# 20260106.net
KiCad netlist of a schematic drawn in EasyEDA Pro
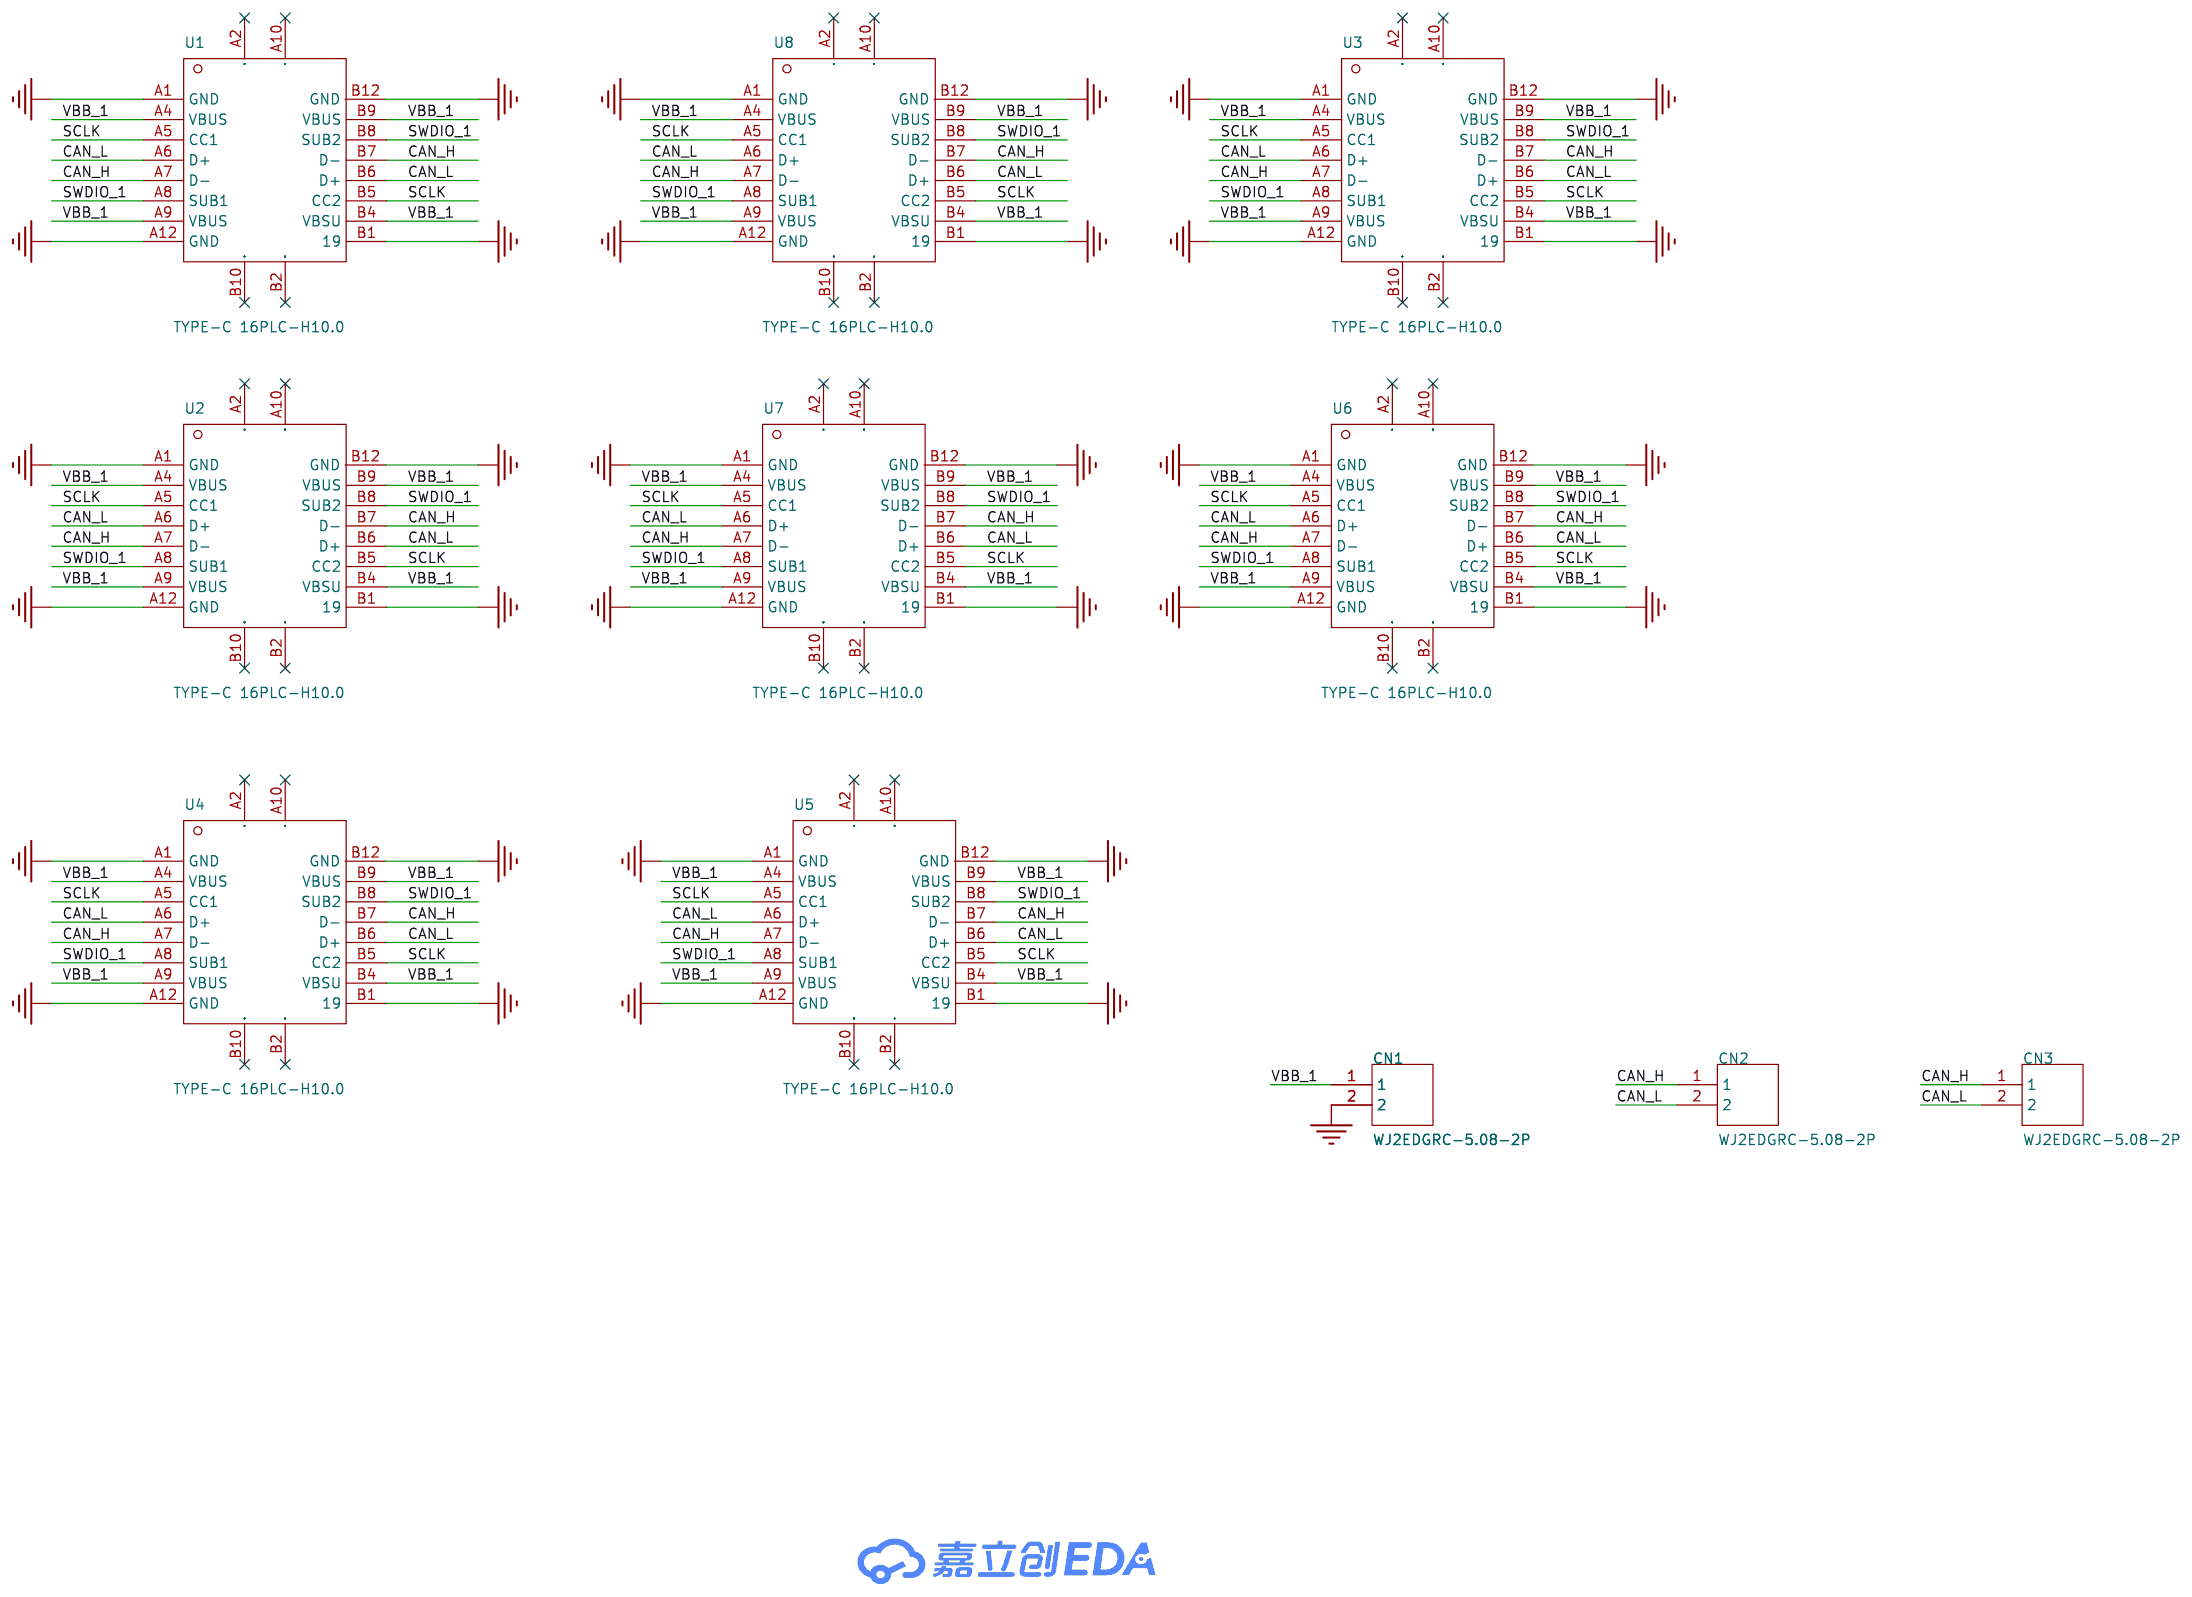
[diagram p0: schematic sheet]

(export (version "E")
  (design (tool "Eeschema 10.0.6"))
  (components
    (comp (ref "CN1")
      (value "WJ2EDGRC-5.08-2P")
      (footprint "easyedapro:CONN-TH_2P-P5.08_WJ2EDGRC-5.08-2P")
      (fields (field (name "Manufacturer") "KANGNEX(康奈克斯电气)"))
      (libsource (lib "easyedapro") (part "WJ2EDGRC-5.08-2P"))
    )
    (comp (ref "CN2")
      (value "WJ2EDGRC-5.08-2P")
      (footprint "easyedapro:CONN-TH_2P-P5.08_WJ2EDGRC-5.08-2P")
      (fields (field (name "Manufacturer") "KANGNEX(康奈克斯电气)"))
      (libsource (lib "easyedapro") (part "WJ2EDGRC-5.08-2P"))
    )
    (comp (ref "CN3")
      (value "WJ2EDGRC-5.08-2P")
      (footprint "easyedapro:CONN-TH_2P-P5.08_WJ2EDGRC-5.08-2P")
      (fields (field (name "Manufacturer") "KANGNEX(康奈克斯电气)"))
      (libsource (lib "easyedapro") (part "WJ2EDGRC-5.08-2P"))
    )
    (comp (ref "U1")
      (value "TYPE-C 16PLC-H10.0")
      (footprint "easyedapro:TYPE-C-TH_16PLC-H10.0")
      (fields (field (name "Manufacturer") "SHOU HAN(首韩)"))
      (libsource (lib "easyedapro") (part "TYPE-C 16PLC-H10.0"))
    )
    (comp (ref "U2")
      (value "TYPE-C 16PLC-H10.0")
      (footprint "easyedapro:TYPE-C-TH_16PLC-H10.0")
      (fields (field (name "Manufacturer") "SHOU HAN(首韩)"))
      (libsource (lib "easyedapro") (part "TYPE-C 16PLC-H10.0"))
    )
    (comp (ref "U3")
      (value "TYPE-C 16PLC-H10.0")
      (footprint "easyedapro:TYPE-C-TH_16PLC-H10.0")
      (fields (field (name "Manufacturer") "SHOU HAN(首韩)"))
      (libsource (lib "easyedapro") (part "TYPE-C 16PLC-H10.0"))
    )
    (comp (ref "U4")
      (value "TYPE-C 16PLC-H10.0")
      (footprint "easyedapro:TYPE-C-TH_16PLC-H10.0")
      (fields (field (name "Manufacturer") "SHOU HAN(首韩)"))
      (libsource (lib "easyedapro") (part "TYPE-C 16PLC-H10.0"))
    )
    (comp (ref "U5")
      (value "TYPE-C 16PLC-H10.0")
      (footprint "easyedapro:TYPE-C-TH_16PLC-H10.0")
      (fields (field (name "Manufacturer") "SHOU HAN(首韩)"))
      (libsource (lib "easyedapro") (part "TYPE-C 16PLC-H10.0"))
    )
    (comp (ref "U6")
      (value "TYPE-C 16PLC-H10.0")
      (footprint "easyedapro:TYPE-C-TH_16PLC-H10.0")
      (fields (field (name "Manufacturer") "SHOU HAN(首韩)"))
      (libsource (lib "easyedapro") (part "TYPE-C 16PLC-H10.0"))
    )
    (comp (ref "U7")
      (value "TYPE-C 16PLC-H10.0")
      (footprint "easyedapro:TYPE-C-TH_16PLC-H10.0")
      (fields (field (name "Manufacturer") "SHOU HAN(首韩)"))
      (libsource (lib "easyedapro") (part "TYPE-C 16PLC-H10.0"))
    )
    (comp (ref "U8")
      (value "TYPE-C 16PLC-H10.0")
      (footprint "easyedapro:TYPE-C-TH_16PLC-H10.0")
      (fields (field (name "Manufacturer") "SHOU HAN(首韩)"))
      (libsource (lib "easyedapro") (part "TYPE-C 16PLC-H10.0"))
    )
  )
  (nets
    (net (code "1") (name "/CAN_H") (class "Default")
      (node (ref "CN2") (pin "1") (pinfunction "1_1") (pintype "unspecified"))
      (node (ref "CN3") (pin "1") (pinfunction "1_1") (pintype "unspecified"))
      (node (ref "U1") (pin "A7") (pinfunction "D-_A7") (pintype "input"))
      (node (ref "U1") (pin "B7") (pinfunction "D-_B7") (pintype "input"))
      (node (ref "U2") (pin "A7") (pinfunction "D-_A7") (pintype "input"))
      (node (ref "U2") (pin "B7") (pinfunction "D-_B7") (pintype "input"))
      (node (ref "U3") (pin "A7") (pinfunction "D-_A7") (pintype "input"))
      (node (ref "U3") (pin "B7") (pinfunction "D-_B7") (pintype "input"))
      (node (ref "U4") (pin "A7") (pinfunction "D-_A7") (pintype "input"))
      (node (ref "U4") (pin "B7") (pinfunction "D-_B7") (pintype "input"))
      (node (ref "U5") (pin "A7") (pinfunction "D-_A7") (pintype "input"))
      (node (ref "U5") (pin "B7") (pinfunction "D-_B7") (pintype "input"))
      (node (ref "U6") (pin "A7") (pinfunction "D-_A7") (pintype "input"))
      (node (ref "U6") (pin "B7") (pinfunction "D-_B7") (pintype "input"))
      (node (ref "U7") (pin "A7") (pinfunction "D-_A7") (pintype "input"))
      (node (ref "U7") (pin "B7") (pinfunction "D-_B7") (pintype "input"))
      (node (ref "U8") (pin "A7") (pinfunction "D-_A7") (pintype "input"))
      (node (ref "U8") (pin "B7") (pinfunction "D-_B7") (pintype "input"))
    )
    (net (code "2") (name "/CAN_L") (class "Default")
      (node (ref "CN2") (pin "2") (pinfunction "2_2") (pintype "unspecified"))
      (node (ref "CN3") (pin "2") (pinfunction "2_2") (pintype "unspecified"))
      (node (ref "U1") (pin "A6") (pinfunction "D+_A6") (pintype "input"))
      (node (ref "U1") (pin "B6") (pinfunction "D+_B6") (pintype "input"))
      (node (ref "U2") (pin "A6") (pinfunction "D+_A6") (pintype "input"))
      (node (ref "U2") (pin "B6") (pinfunction "D+_B6") (pintype "input"))
      (node (ref "U3") (pin "A6") (pinfunction "D+_A6") (pintype "input"))
      (node (ref "U3") (pin "B6") (pinfunction "D+_B6") (pintype "input"))
      (node (ref "U4") (pin "A6") (pinfunction "D+_A6") (pintype "input"))
      (node (ref "U4") (pin "B6") (pinfunction "D+_B6") (pintype "input"))
      (node (ref "U5") (pin "A6") (pinfunction "D+_A6") (pintype "input"))
      (node (ref "U5") (pin "B6") (pinfunction "D+_B6") (pintype "input"))
      (node (ref "U6") (pin "A6") (pinfunction "D+_A6") (pintype "input"))
      (node (ref "U6") (pin "B6") (pinfunction "D+_B6") (pintype "input"))
      (node (ref "U7") (pin "A6") (pinfunction "D+_A6") (pintype "input"))
      (node (ref "U7") (pin "B6") (pinfunction "D+_B6") (pintype "input"))
      (node (ref "U8") (pin "A6") (pinfunction "D+_A6") (pintype "input"))
      (node (ref "U8") (pin "B6") (pinfunction "D+_B6") (pintype "input"))
    )
    (net (code "3") (name "/SCLK") (class "Default")
      (node (ref "U1") (pin "A5") (pinfunction "CC1_A5") (pintype "input"))
      (node (ref "U1") (pin "B5") (pinfunction "CC2_B5") (pintype "input"))
      (node (ref "U2") (pin "A5") (pinfunction "CC1_A5") (pintype "input"))
      (node (ref "U2") (pin "B5") (pinfunction "CC2_B5") (pintype "input"))
      (node (ref "U3") (pin "A5") (pinfunction "CC1_A5") (pintype "input"))
      (node (ref "U3") (pin "B5") (pinfunction "CC2_B5") (pintype "input"))
      (node (ref "U4") (pin "A5") (pinfunction "CC1_A5") (pintype "input"))
      (node (ref "U4") (pin "B5") (pinfunction "CC2_B5") (pintype "input"))
      (node (ref "U5") (pin "A5") (pinfunction "CC1_A5") (pintype "input"))
      (node (ref "U5") (pin "B5") (pinfunction "CC2_B5") (pintype "input"))
      (node (ref "U6") (pin "A5") (pinfunction "CC1_A5") (pintype "input"))
      (node (ref "U6") (pin "B5") (pinfunction "CC2_B5") (pintype "input"))
      (node (ref "U7") (pin "A5") (pinfunction "CC1_A5") (pintype "input"))
      (node (ref "U7") (pin "B5") (pinfunction "CC2_B5") (pintype "input"))
      (node (ref "U8") (pin "A5") (pinfunction "CC1_A5") (pintype "input"))
      (node (ref "U8") (pin "B5") (pinfunction "CC2_B5") (pintype "input"))
    )
    (net (code "4") (name "/SWDIO_1") (class "Default")
      (node (ref "U1") (pin "A8") (pinfunction "SUB1_A8") (pintype "input"))
      (node (ref "U1") (pin "B8") (pinfunction "SUB2_B8") (pintype "input"))
      (node (ref "U2") (pin "A8") (pinfunction "SUB1_A8") (pintype "input"))
      (node (ref "U2") (pin "B8") (pinfunction "SUB2_B8") (pintype "input"))
      (node (ref "U3") (pin "A8") (pinfunction "SUB1_A8") (pintype "input"))
      (node (ref "U3") (pin "B8") (pinfunction "SUB2_B8") (pintype "input"))
      (node (ref "U4") (pin "A8") (pinfunction "SUB1_A8") (pintype "input"))
      (node (ref "U4") (pin "B8") (pinfunction "SUB2_B8") (pintype "input"))
      (node (ref "U5") (pin "A8") (pinfunction "SUB1_A8") (pintype "input"))
      (node (ref "U5") (pin "B8") (pinfunction "SUB2_B8") (pintype "input"))
      (node (ref "U6") (pin "A8") (pinfunction "SUB1_A8") (pintype "input"))
      (node (ref "U6") (pin "B8") (pinfunction "SUB2_B8") (pintype "input"))
      (node (ref "U7") (pin "A8") (pinfunction "SUB1_A8") (pintype "input"))
      (node (ref "U7") (pin "B8") (pinfunction "SUB2_B8") (pintype "input"))
      (node (ref "U8") (pin "A8") (pinfunction "SUB1_A8") (pintype "input"))
      (node (ref "U8") (pin "B8") (pinfunction "SUB2_B8") (pintype "input"))
    )
    (net (code "5") (name "/VBB_1") (class "Default")
      (node (ref "CN1") (pin "1") (pinfunction "1_1") (pintype "unspecified"))
      (node (ref "U1") (pin "A4") (pinfunction "VBUS_A4") (pintype "input"))
      (node (ref "U1") (pin "A9") (pinfunction "VBUS_A9") (pintype "input"))
      (node (ref "U1") (pin "B4") (pinfunction "VBSU_B4") (pintype "input"))
      (node (ref "U1") (pin "B9") (pinfunction "VBUS_B9") (pintype "input"))
      (node (ref "U2") (pin "A4") (pinfunction "VBUS_A4") (pintype "input"))
      (node (ref "U2") (pin "A9") (pinfunction "VBUS_A9") (pintype "input"))
      (node (ref "U2") (pin "B4") (pinfunction "VBSU_B4") (pintype "input"))
      (node (ref "U2") (pin "B9") (pinfunction "VBUS_B9") (pintype "input"))
      (node (ref "U3") (pin "A4") (pinfunction "VBUS_A4") (pintype "input"))
      (node (ref "U3") (pin "A9") (pinfunction "VBUS_A9") (pintype "input"))
      (node (ref "U3") (pin "B4") (pinfunction "VBSU_B4") (pintype "input"))
      (node (ref "U3") (pin "B9") (pinfunction "VBUS_B9") (pintype "input"))
      (node (ref "U4") (pin "A4") (pinfunction "VBUS_A4") (pintype "input"))
      (node (ref "U4") (pin "A9") (pinfunction "VBUS_A9") (pintype "input"))
      (node (ref "U4") (pin "B4") (pinfunction "VBSU_B4") (pintype "input"))
      (node (ref "U4") (pin "B9") (pinfunction "VBUS_B9") (pintype "input"))
      (node (ref "U5") (pin "A4") (pinfunction "VBUS_A4") (pintype "input"))
      (node (ref "U5") (pin "A9") (pinfunction "VBUS_A9") (pintype "input"))
      (node (ref "U5") (pin "B4") (pinfunction "VBSU_B4") (pintype "input"))
      (node (ref "U5") (pin "B9") (pinfunction "VBUS_B9") (pintype "input"))
      (node (ref "U6") (pin "A4") (pinfunction "VBUS_A4") (pintype "input"))
      (node (ref "U6") (pin "A9") (pinfunction "VBUS_A9") (pintype "input"))
      (node (ref "U6") (pin "B4") (pinfunction "VBSU_B4") (pintype "input"))
      (node (ref "U6") (pin "B9") (pinfunction "VBUS_B9") (pintype "input"))
      (node (ref "U7") (pin "A4") (pinfunction "VBUS_A4") (pintype "input"))
      (node (ref "U7") (pin "A9") (pinfunction "VBUS_A9") (pintype "input"))
      (node (ref "U7") (pin "B4") (pinfunction "VBSU_B4") (pintype "input"))
      (node (ref "U7") (pin "B9") (pinfunction "VBUS_B9") (pintype "input"))
      (node (ref "U8") (pin "A4") (pinfunction "VBUS_A4") (pintype "input"))
      (node (ref "U8") (pin "A9") (pinfunction "VBUS_A9") (pintype "input"))
      (node (ref "U8") (pin "B4") (pinfunction "VBSU_B4") (pintype "input"))
      (node (ref "U8") (pin "B9") (pinfunction "VBUS_B9") (pintype "input"))
    )
    (net (code "6") (name "GND") (class "Default")
      (node (ref "CN1") (pin "2") (pinfunction "2_2") (pintype "unspecified"))
      (node (ref "U1") (pin "A1") (pinfunction "GND_A1") (pintype "input"))
      (node (ref "U1") (pin "A12") (pinfunction "GND_A12") (pintype "input"))
      (node (ref "U1") (pin "B1") (pinfunction "19_B1") (pintype "input"))
      (node (ref "U1") (pin "B12") (pinfunction "GND_B12") (pintype "input"))
      (node (ref "U2") (pin "A1") (pinfunction "GND_A1") (pintype "input"))
      (node (ref "U2") (pin "A12") (pinfunction "GND_A12") (pintype "input"))
      (node (ref "U2") (pin "B1") (pinfunction "19_B1") (pintype "input"))
      (node (ref "U2") (pin "B12") (pinfunction "GND_B12") (pintype "input"))
      (node (ref "U3") (pin "A1") (pinfunction "GND_A1") (pintype "input"))
      (node (ref "U3") (pin "A12") (pinfunction "GND_A12") (pintype "input"))
      (node (ref "U3") (pin "B1") (pinfunction "19_B1") (pintype "input"))
      (node (ref "U3") (pin "B12") (pinfunction "GND_B12") (pintype "input"))
      (node (ref "U4") (pin "A1") (pinfunction "GND_A1") (pintype "input"))
      (node (ref "U4") (pin "A12") (pinfunction "GND_A12") (pintype "input"))
      (node (ref "U4") (pin "B1") (pinfunction "19_B1") (pintype "input"))
      (node (ref "U4") (pin "B12") (pinfunction "GND_B12") (pintype "input"))
      (node (ref "U5") (pin "A1") (pinfunction "GND_A1") (pintype "input"))
      (node (ref "U5") (pin "A12") (pinfunction "GND_A12") (pintype "input"))
      (node (ref "U5") (pin "B1") (pinfunction "19_B1") (pintype "input"))
      (node (ref "U5") (pin "B12") (pinfunction "GND_B12") (pintype "input"))
      (node (ref "U6") (pin "A1") (pinfunction "GND_A1") (pintype "input"))
      (node (ref "U6") (pin "A12") (pinfunction "GND_A12") (pintype "input"))
      (node (ref "U6") (pin "B1") (pinfunction "19_B1") (pintype "input"))
      (node (ref "U6") (pin "B12") (pinfunction "GND_B12") (pintype "input"))
      (node (ref "U7") (pin "A1") (pinfunction "GND_A1") (pintype "input"))
      (node (ref "U7") (pin "A12") (pinfunction "GND_A12") (pintype "input"))
      (node (ref "U7") (pin "B1") (pinfunction "19_B1") (pintype "input"))
      (node (ref "U7") (pin "B12") (pinfunction "GND_B12") (pintype "input"))
      (node (ref "U8") (pin "A1") (pinfunction "GND_A1") (pintype "input"))
      (node (ref "U8") (pin "A12") (pinfunction "GND_A12") (pintype "input"))
      (node (ref "U8") (pin "B1") (pinfunction "19_B1") (pintype "input"))
      (node (ref "U8") (pin "B12") (pinfunction "GND_B12") (pintype "input"))
    )
    (net (code "7") (name "unconnected-(U1-GND1-PadA2)") (class "Default")
      (node (ref "U1") (pin "A2") (pinfunction "GND1_A2") (pintype "input+no_connect"))
    )
    (net (code "8") (name "unconnected-(U1-GND2-PadA10)") (class "Default")
      (node (ref "U1") (pin "A10") (pinfunction "GND2_A10") (pintype "input+no_connect"))
    )
    (net (code "9") (name "unconnected-(U1-GND3-PadB10)") (class "Default")
      (node (ref "U1") (pin "B10") (pinfunction "GND3_B10") (pintype "input+no_connect"))
    )
    (net (code "10") (name "unconnected-(U1-GND4-PadB2)") (class "Default")
      (node (ref "U1") (pin "B2") (pinfunction "GND4_B2") (pintype "input+no_connect"))
    )
    (net (code "11") (name "unconnected-(U2-GND1-PadA2)") (class "Default")
      (node (ref "U2") (pin "A2") (pinfunction "GND1_A2") (pintype "input+no_connect"))
    )
    (net (code "12") (name "unconnected-(U2-GND2-PadA10)") (class "Default")
      (node (ref "U2") (pin "A10") (pinfunction "GND2_A10") (pintype "input+no_connect"))
    )
    (net (code "13") (name "unconnected-(U2-GND3-PadB10)") (class "Default")
      (node (ref "U2") (pin "B10") (pinfunction "GND3_B10") (pintype "input+no_connect"))
    )
    (net (code "14") (name "unconnected-(U2-GND4-PadB2)") (class "Default")
      (node (ref "U2") (pin "B2") (pinfunction "GND4_B2") (pintype "input+no_connect"))
    )
    (net (code "15") (name "unconnected-(U3-GND1-PadA2)") (class "Default")
      (node (ref "U3") (pin "A2") (pinfunction "GND1_A2") (pintype "input+no_connect"))
    )
    (net (code "16") (name "unconnected-(U3-GND2-PadA10)") (class "Default")
      (node (ref "U3") (pin "A10") (pinfunction "GND2_A10") (pintype "input+no_connect"))
    )
    (net (code "17") (name "unconnected-(U3-GND3-PadB10)") (class "Default")
      (node (ref "U3") (pin "B10") (pinfunction "GND3_B10") (pintype "input+no_connect"))
    )
    (net (code "18") (name "unconnected-(U3-GND4-PadB2)") (class "Default")
      (node (ref "U3") (pin "B2") (pinfunction "GND4_B2") (pintype "input+no_connect"))
    )
    (net (code "19") (name "unconnected-(U4-GND1-PadA2)") (class "Default")
      (node (ref "U4") (pin "A2") (pinfunction "GND1_A2") (pintype "input+no_connect"))
    )
    (net (code "20") (name "unconnected-(U4-GND2-PadA10)") (class "Default")
      (node (ref "U4") (pin "A10") (pinfunction "GND2_A10") (pintype "input+no_connect"))
    )
    (net (code "21") (name "unconnected-(U4-GND3-PadB10)") (class "Default")
      (node (ref "U4") (pin "B10") (pinfunction "GND3_B10") (pintype "input+no_connect"))
    )
    (net (code "22") (name "unconnected-(U4-GND4-PadB2)") (class "Default")
      (node (ref "U4") (pin "B2") (pinfunction "GND4_B2") (pintype "input+no_connect"))
    )
    (net (code "23") (name "unconnected-(U5-GND1-PadA2)") (class "Default")
      (node (ref "U5") (pin "A2") (pinfunction "GND1_A2") (pintype "input+no_connect"))
    )
    (net (code "24") (name "unconnected-(U5-GND2-PadA10)") (class "Default")
      (node (ref "U5") (pin "A10") (pinfunction "GND2_A10") (pintype "input+no_connect"))
    )
    (net (code "25") (name "unconnected-(U5-GND3-PadB10)") (class "Default")
      (node (ref "U5") (pin "B10") (pinfunction "GND3_B10") (pintype "input+no_connect"))
    )
    (net (code "26") (name "unconnected-(U5-GND4-PadB2)") (class "Default")
      (node (ref "U5") (pin "B2") (pinfunction "GND4_B2") (pintype "input+no_connect"))
    )
    (net (code "27") (name "unconnected-(U6-GND1-PadA2)") (class "Default")
      (node (ref "U6") (pin "A2") (pinfunction "GND1_A2") (pintype "input+no_connect"))
    )
    (net (code "28") (name "unconnected-(U6-GND2-PadA10)") (class "Default")
      (node (ref "U6") (pin "A10") (pinfunction "GND2_A10") (pintype "input+no_connect"))
    )
    (net (code "29") (name "unconnected-(U6-GND3-PadB10)") (class "Default")
      (node (ref "U6") (pin "B10") (pinfunction "GND3_B10") (pintype "input+no_connect"))
    )
    (net (code "30") (name "unconnected-(U6-GND4-PadB2)") (class "Default")
      (node (ref "U6") (pin "B2") (pinfunction "GND4_B2") (pintype "input+no_connect"))
    )
    (net (code "31") (name "unconnected-(U7-GND1-PadA2)") (class "Default")
      (node (ref "U7") (pin "A2") (pinfunction "GND1_A2") (pintype "input+no_connect"))
    )
    (net (code "32") (name "unconnected-(U7-GND2-PadA10)") (class "Default")
      (node (ref "U7") (pin "A10") (pinfunction "GND2_A10") (pintype "input+no_connect"))
    )
    (net (code "33") (name "unconnected-(U7-GND3-PadB10)") (class "Default")
      (node (ref "U7") (pin "B10") (pinfunction "GND3_B10") (pintype "input+no_connect"))
    )
    (net (code "34") (name "unconnected-(U7-GND4-PadB2)") (class "Default")
      (node (ref "U7") (pin "B2") (pinfunction "GND4_B2") (pintype "input+no_connect"))
    )
    (net (code "35") (name "unconnected-(U8-GND1-PadA2)") (class "Default")
      (node (ref "U8") (pin "A2") (pinfunction "GND1_A2") (pintype "input+no_connect"))
    )
    (net (code "36") (name "unconnected-(U8-GND2-PadA10)") (class "Default")
      (node (ref "U8") (pin "A10") (pinfunction "GND2_A10") (pintype "input+no_connect"))
    )
    (net (code "37") (name "unconnected-(U8-GND3-PadB10)") (class "Default")
      (node (ref "U8") (pin "B10") (pinfunction "GND3_B10") (pintype "input+no_connect"))
    )
    (net (code "38") (name "unconnected-(U8-GND4-PadB2)") (class "Default")
      (node (ref "U8") (pin "B2") (pinfunction "GND4_B2") (pintype "input+no_connect"))
    )
  )
)
